# 2_MCU.net
KiCad netlist of a schematic drawn in Altium Designer
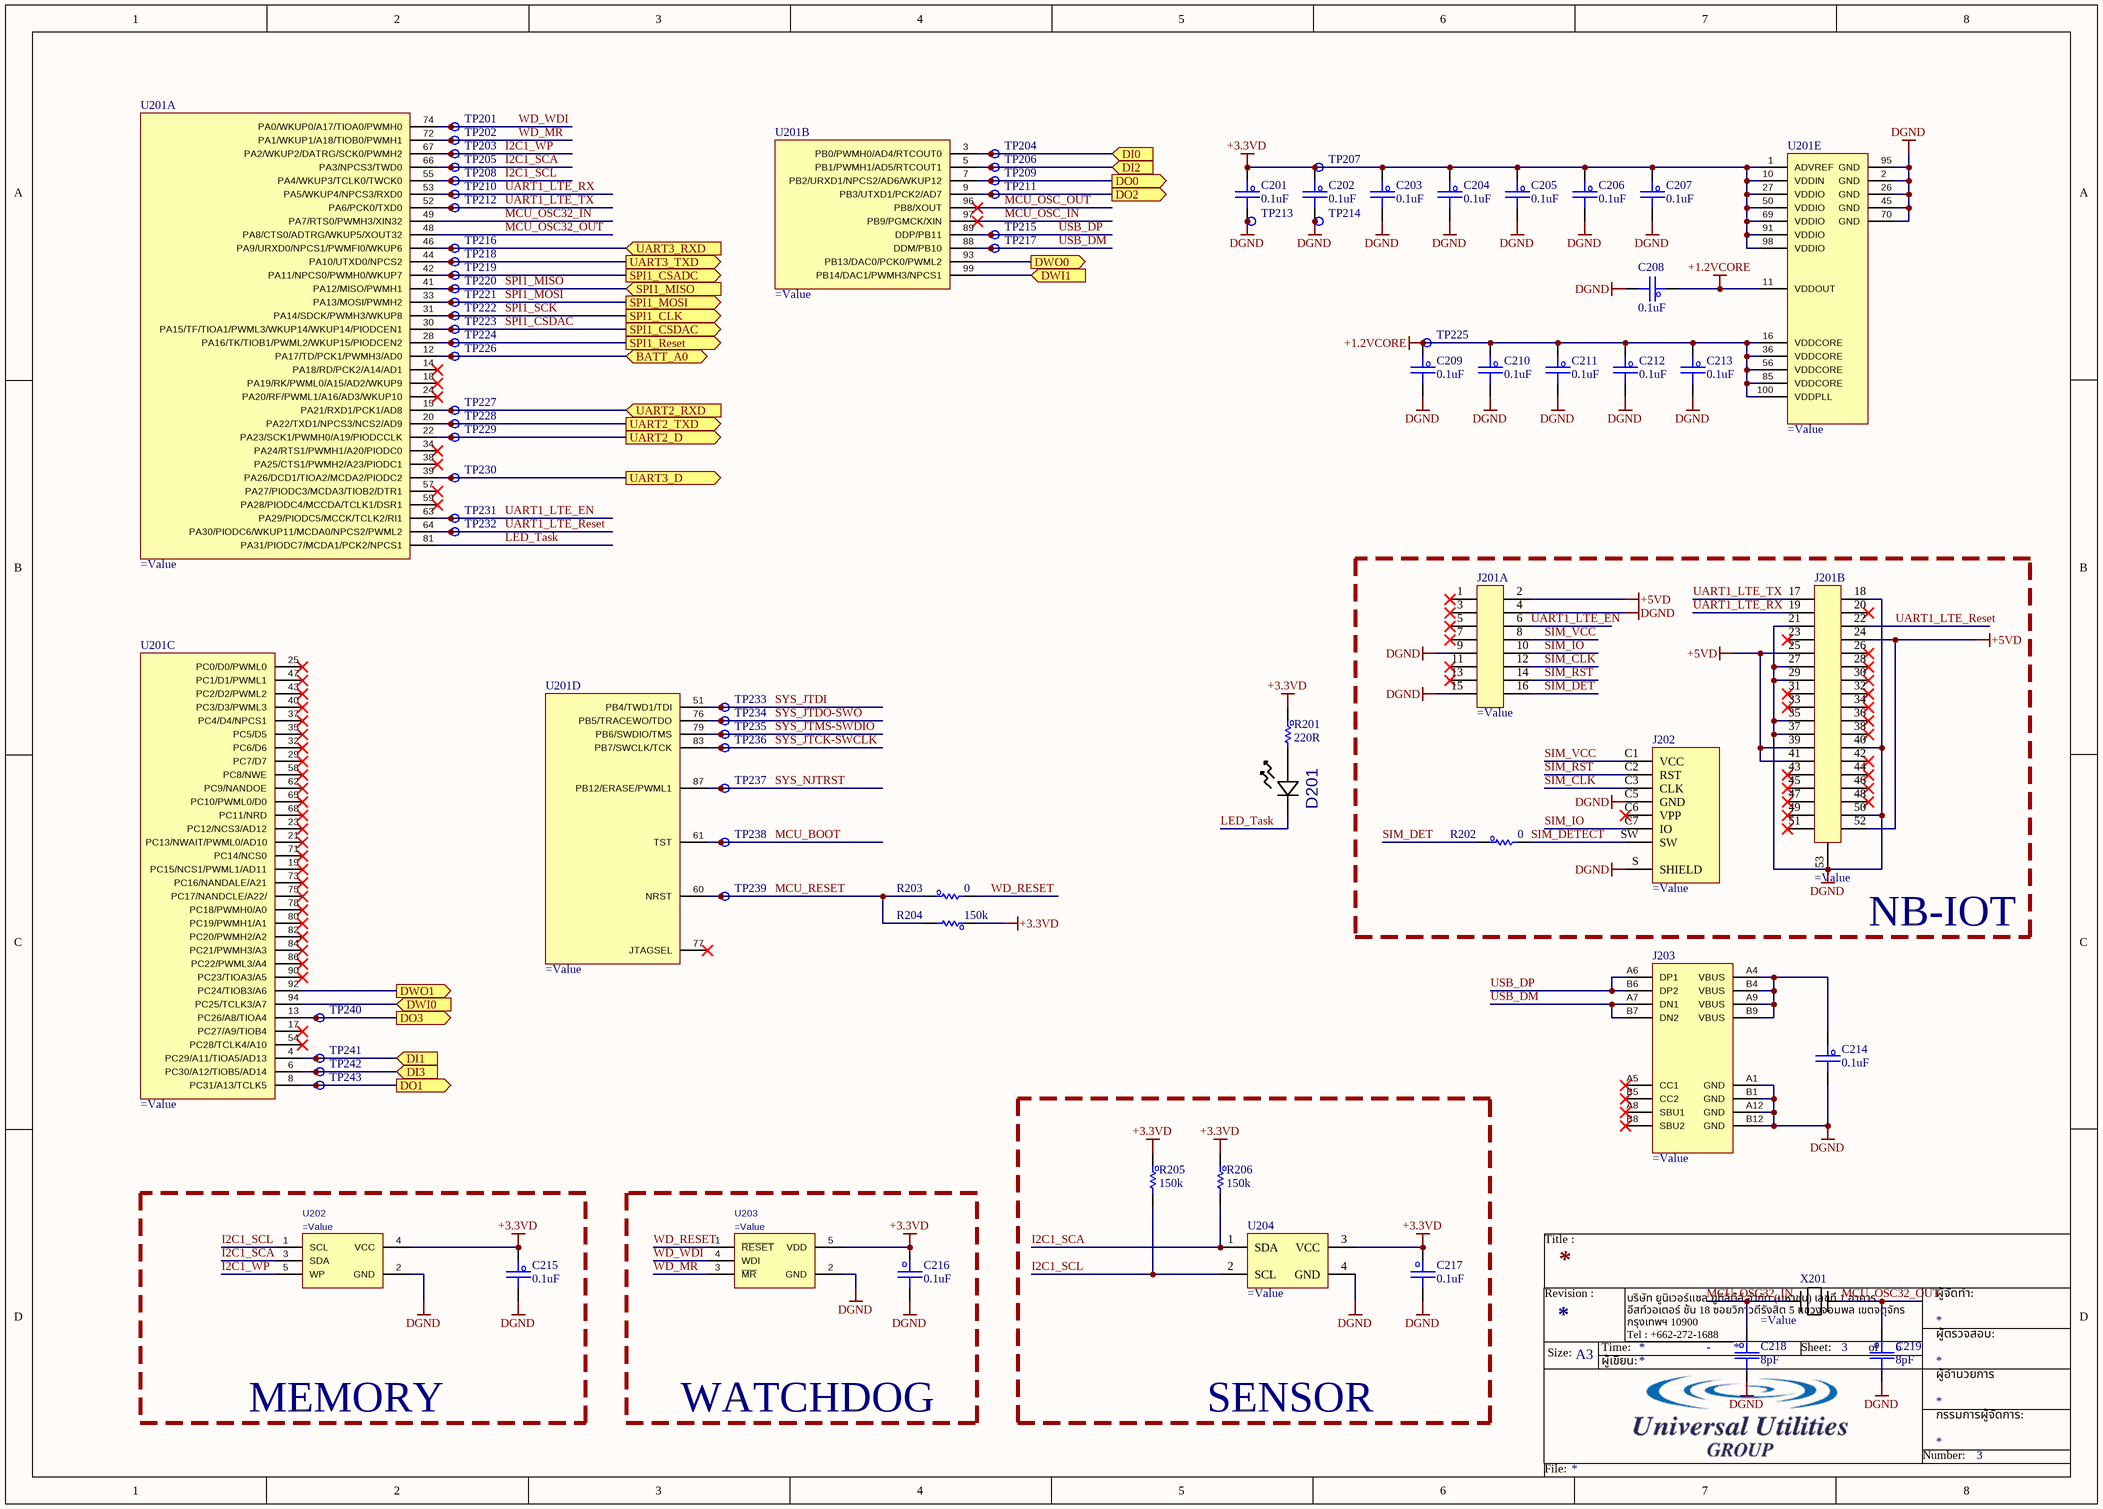
[diagram p0: 2_MCU.SchDoc]

(export (version "E")
  (design (tool "Eeschema 10.0.6"))
  (components
    (comp (ref "C201")
      (value "0.1uF")
      (footprint "C_0603")
      (description "CAP CER 0.1UF 50V X7R 0603")
      (fields (field (name "MANUFACTURER") "KEMET") (field (name "PARTNUMBER") "C0603C104K5RACTU"))
      (libsource (lib "UUSymbol") (part "C_Capacitor"))
    )
    (comp (ref "C202")
      (value "0.1uF")
      (footprint "C_0603")
      (description "CAP CER 0.1UF 50V X7R 0603")
      (fields (field (name "MANUFACTURER") "KEMET") (field (name "PARTNUMBER") "C0603C104K5RACTU"))
      (libsource (lib "UUSymbol") (part "C_Capacitor"))
    )
    (comp (ref "C203")
      (value "0.1uF")
      (footprint "C_0603")
      (description "CAP CER 0.1UF 50V X7R 0603")
      (fields (field (name "MANUFACTURER") "KEMET") (field (name "PARTNUMBER") "C0603C104K5RACTU"))
      (libsource (lib "UUSymbol") (part "C_Capacitor"))
    )
    (comp (ref "C204")
      (value "0.1uF")
      (footprint "C_0603")
      (description "CAP CER 0.1UF 50V X7R 0603")
      (fields (field (name "MANUFACTURER") "KEMET") (field (name "PARTNUMBER") "C0603C104K5RACTU"))
      (libsource (lib "UUSymbol") (part "C_Capacitor"))
    )
    (comp (ref "C205")
      (value "0.1uF")
      (footprint "C_0603")
      (description "CAP CER 0.1UF 50V X7R 0603")
      (fields (field (name "MANUFACTURER") "KEMET") (field (name "PARTNUMBER") "C0603C104K5RACTU"))
      (libsource (lib "UUSymbol") (part "C_Capacitor"))
    )
    (comp (ref "C206")
      (value "0.1uF")
      (footprint "C_0603")
      (description "CAP CER 0.1UF 50V X7R 0603")
      (fields (field (name "MANUFACTURER") "KEMET") (field (name "PARTNUMBER") "C0603C104K5RACTU"))
      (libsource (lib "UUSymbol") (part "C_Capacitor"))
    )
    (comp (ref "C207")
      (value "0.1uF")
      (footprint "C_0603")
      (description "CAP CER 0.1UF 50V X7R 0603")
      (fields (field (name "MANUFACTURER") "KEMET") (field (name "PARTNUMBER") "C0603C104K5RACTU"))
      (libsource (lib "UUSymbol") (part "C_Capacitor"))
    )
    (comp (ref "C208")
      (value "0.1uF")
      (footprint "C_0603")
      (description "CAP CER 0.1UF 50V X7R 0603")
      (fields (field (name "MANUFACTURER") "KEMET") (field (name "PARTNUMBER") "C0603C104K5RACTU"))
      (libsource (lib "UUSymbol") (part "C_Capacitor"))
    )
    (comp (ref "C209")
      (value "0.1uF")
      (footprint "C_0603")
      (description "CAP CER 0.1UF 50V X7R 0603")
      (fields (field (name "MANUFACTURER") "KEMET") (field (name "PARTNUMBER") "C0603C104K5RACTU"))
      (libsource (lib "UUSymbol") (part "C_Capacitor"))
    )
    (comp (ref "C210")
      (value "0.1uF")
      (footprint "C_0603")
      (description "CAP CER 0.1UF 50V X7R 0603")
      (fields (field (name "MANUFACTURER") "KEMET") (field (name "PARTNUMBER") "C0603C104K5RACTU"))
      (libsource (lib "UUSymbol") (part "C_Capacitor"))
    )
    (comp (ref "C211")
      (value "0.1uF")
      (footprint "C_0603")
      (description "CAP CER 0.1UF 50V X7R 0603")
      (fields (field (name "MANUFACTURER") "KEMET") (field (name "PARTNUMBER") "C0603C104K5RACTU"))
      (libsource (lib "UUSymbol") (part "C_Capacitor"))
    )
    (comp (ref "C212")
      (value "0.1uF")
      (footprint "C_0603")
      (description "CAP CER 0.1UF 50V X7R 0603")
      (fields (field (name "MANUFACTURER") "KEMET") (field (name "PARTNUMBER") "C0603C104K5RACTU"))
      (libsource (lib "UUSymbol") (part "C_Capacitor"))
    )
    (comp (ref "C213")
      (value "0.1uF")
      (footprint "C_0603")
      (description "CAP CER 0.1UF 50V X7R 0603")
      (fields (field (name "MANUFACTURER") "KEMET") (field (name "PARTNUMBER") "C0603C104K5RACTU"))
      (libsource (lib "UUSymbol") (part "C_Capacitor"))
    )
    (comp (ref "C214")
      (value "0.1uF")
      (footprint "C_0603")
      (description "CAP CER 0.1UF 50V X7R 0603")
      (fields (field (name "MANUFACTURER") "KEMET") (field (name "PARTNUMBER") "C0603C104K5RACTU"))
      (libsource (lib "UUSymbol") (part "C_Capacitor"))
    )
    (comp (ref "C215")
      (value "0.1uF")
      (footprint "C_0603")
      (description "CAP CER 0.1UF 50V X7R 0603")
      (fields (field (name "MANUFACTURER") "KEMET") (field (name "PARTNUMBER") "C0603C104K5RACTU"))
      (libsource (lib "UUSymbol") (part "C_Capacitor"))
    )
    (comp (ref "C216")
      (value "0.1uF")
      (footprint "C_0603")
      (description "CAP CER 0.1UF 50V X7R 0603")
      (fields (field (name "MANUFACTURER") "KEMET") (field (name "PARTNUMBER") "C0603C104K5RACTU"))
      (libsource (lib "UUSymbol") (part "C_Capacitor"))
    )
    (comp (ref "C217")
      (value "0.1uF")
      (footprint "C_0603")
      (description "CAP CER 0.1UF 50V X7R 0603")
      (fields (field (name "MANUFACTURER") "KEMET") (field (name "PARTNUMBER") "C0603C104K5RACTU"))
      (libsource (lib "UUSymbol") (part "C_Capacitor"))
    )
    (comp (ref "C218")
      (value "8pF")
      (footprint "C_0603")
      (description "Capacitor")
      (fields (field (name "MANUFACTURER") "KEMET") (field (name "PARTNUMBER") "CBR06C809B5GAC"))
      (libsource (lib "UUSymbol") (part "C_Capacitor"))
    )
    (comp (ref "C219")
      (value "8pF")
      (footprint "C_0603")
      (description "Capacitor")
      (fields (field (name "MANUFACTURER") "KEMET") (field (name "PARTNUMBER") "CBR06C809B5GAC"))
      (libsource (lib "UUSymbol") (part "C_Capacitor"))
    )
    (comp (ref "D201")
      (value "~")
      (footprint "LED_0VS75000_WRE")
      (description "LED BLUE CLEAR 0603 SMD")
      (fields (field (name "MANUFACTURER") "Wurth Electronics") (field (name "PARTNUMBER") "150060VS75000"))
      (libsource (lib "UUSymbol") (part "D_LED_150060BS75000"))
    )
    (comp (ref "J201")
      (value "~")
      (footprint "TE_2041119-1")
      (description "CONN PCI EXP MINI FEMALE 52POS")
      (fields
        (field (name "PARTNUMBER") "2041119-1")
        (field (name "MANUFACTURER") "TE Connectivity AMP Connectors")
      )
      (libsource (lib "UUSymbol") (part "CON_PCI-E-52P"))
    )
    (comp (ref "J202")
      (value "~")
      (footprint "SIM8060-6-1-14-00-A_REVA")
      (description "CONN SIM NANO HINGED 6P W/SWITCH")
      (fields (field (name "PARTNUMBER") "SIM8060-6-1-14-00-A") (field (name "MANUFACTURER") "GCT"))
      (libsource (lib "UUSymbol") (part "CON_SIM_Nano_Top"))
    )
    (comp (ref "J203")
      (value "~")
      (footprint "2137160001_MOL_2137160001(Primary)")
      (description "CONN RCPT USB2.0 TYPE C 24POS RA")
      (fields (field (name "PARTNUMBER") "2137160001") (field (name "MANUFACTURER") "Molex"))
      (libsource (lib "UUSymbol") (part "CON_USBC"))
    )
    (comp (ref "R201")
      (value "220R")
      (footprint "R_0603")
      (description "RES SMD 220 OHM 1% 1/10W 0603")
      (fields (field (name "MANUFACTURER") "Vishay Dale") (field (name "PARTNUMBER") "CRCW0603220RFKEAC"))
      (libsource (lib "UUSymbol") (part "R_Resister"))
    )
    (comp (ref "R202")
      (value "0")
      (footprint "R_0603")
      (description "RES SMD 0 OHM JUMP 1/10W 0603")
      (fields (field (name "MANUFACTURER") "Vishay Dale") (field (name "PARTNUMBER") "CRCW06030000Z0EBC"))
      (libsource (lib "UUSymbol") (part "R_Resister"))
    )
    (comp (ref "R203")
      (value "0")
      (footprint "R_0603")
      (description "RES SMD 0 OHM JUMP 1/10W 0603")
      (fields (field (name "MANUFACTURER") "Vishay Dale") (field (name "PARTNUMBER") "CRCW06030000Z0EBC"))
      (libsource (lib "UUSymbol") (part "R_Resister"))
    )
    (comp (ref "R204")
      (value "150k")
      (footprint "R_0603")
      (description "RES SMD 150K OHM 1% 1/10W 0603")
      (fields (field (name "MANUFACTURER") "Vishay Dale") (field (name "PARTNUMBER") "CRCW0603150KFKEAC"))
      (libsource (lib "UUSymbol") (part "R_Resister"))
    )
    (comp (ref "R205")
      (value "150k")
      (footprint "R_0603")
      (description "RES SMD 150K OHM 1% 1/10W 0603")
      (fields (field (name "MANUFACTURER") "Vishay Dale") (field (name "PARTNUMBER") "CRCW0603150KFKEAC"))
      (libsource (lib "UUSymbol") (part "R_Resister"))
    )
    (comp (ref "R206")
      (value "150k")
      (footprint "R_0603")
      (description "RES SMD 150K OHM 1% 1/10W 0603")
      (fields (field (name "MANUFACTURER") "Vishay Dale") (field (name "PARTNUMBER") "CRCW0603150KFKEAC"))
      (libsource (lib "UUSymbol") (part "R_Resister"))
    )
    (comp (ref "TP201")
      (value "~")
      (footprint "TP_Testpoint")
      (description "TestPoint")
      (libsource (lib "UUSymbol") (part "TP_TestPoint"))
    )
    (comp (ref "TP202")
      (value "~")
      (footprint "TP_Testpoint")
      (description "TestPoint")
      (libsource (lib "UUSymbol") (part "TP_TestPoint"))
    )
    (comp (ref "TP203")
      (value "~")
      (footprint "TP_Testpoint")
      (description "TestPoint")
      (libsource (lib "UUSymbol") (part "TP_TestPoint"))
    )
    (comp (ref "TP204")
      (value "~")
      (footprint "TP_Testpoint")
      (description "TestPoint")
      (libsource (lib "UUSymbol") (part "TP_TestPoint"))
    )
    (comp (ref "TP205")
      (value "~")
      (footprint "TP_Testpoint")
      (description "TestPoint")
      (libsource (lib "UUSymbol") (part "TP_TestPoint"))
    )
    (comp (ref "TP206")
      (value "~")
      (footprint "TP_Testpoint")
      (description "TestPoint")
      (libsource (lib "UUSymbol") (part "TP_TestPoint"))
    )
    (comp (ref "TP207")
      (value "~")
      (footprint "TP_Testpoint")
      (description "TestPoint")
      (libsource (lib "UUSymbol") (part "TP_TestPoint"))
    )
    (comp (ref "TP208")
      (value "~")
      (footprint "TP_Testpoint")
      (description "TestPoint")
      (libsource (lib "UUSymbol") (part "TP_TestPoint"))
    )
    (comp (ref "TP209")
      (value "~")
      (footprint "TP_Testpoint")
      (description "TestPoint")
      (libsource (lib "UUSymbol") (part "TP_TestPoint"))
    )
    (comp (ref "TP210")
      (value "~")
      (footprint "TP_Testpoint")
      (description "TestPoint")
      (libsource (lib "UUSymbol") (part "TP_TestPoint"))
    )
    (comp (ref "TP211")
      (value "~")
      (footprint "TP_Testpoint")
      (description "TestPoint")
      (libsource (lib "UUSymbol") (part "TP_TestPoint"))
    )
    (comp (ref "TP212")
      (value "~")
      (footprint "TP_Testpoint")
      (description "TestPoint")
      (libsource (lib "UUSymbol") (part "TP_TestPoint"))
    )
    (comp (ref "TP213")
      (value "~")
      (footprint "TP_Testpoint")
      (description "TestPoint")
      (libsource (lib "UUSymbol") (part "TP_TestPoint"))
    )
    (comp (ref "TP214")
      (value "~")
      (footprint "TP_Testpoint")
      (description "TestPoint")
      (libsource (lib "UUSymbol") (part "TP_TestPoint"))
    )
    (comp (ref "TP215")
      (value "~")
      (footprint "TP_Testpoint")
      (description "TestPoint")
      (libsource (lib "UUSymbol") (part "TP_TestPoint"))
    )
    (comp (ref "TP216")
      (value "~")
      (footprint "TP_Testpoint")
      (description "TestPoint")
      (libsource (lib "UUSymbol") (part "TP_TestPoint"))
    )
    (comp (ref "TP217")
      (value "~")
      (footprint "TP_Testpoint")
      (description "TestPoint")
      (libsource (lib "UUSymbol") (part "TP_TestPoint"))
    )
    (comp (ref "TP218")
      (value "~")
      (footprint "TP_Testpoint")
      (description "TestPoint")
      (libsource (lib "UUSymbol") (part "TP_TestPoint"))
    )
    (comp (ref "TP219")
      (value "~")
      (footprint "TP_Testpoint")
      (description "TestPoint")
      (libsource (lib "UUSymbol") (part "TP_TestPoint"))
    )
    (comp (ref "TP220")
      (value "~")
      (footprint "TP_Testpoint")
      (description "TestPoint")
      (libsource (lib "UUSymbol") (part "TP_TestPoint"))
    )
    (comp (ref "TP221")
      (value "~")
      (footprint "TP_Testpoint")
      (description "TestPoint")
      (libsource (lib "UUSymbol") (part "TP_TestPoint"))
    )
    (comp (ref "TP222")
      (value "~")
      (footprint "TP_Testpoint")
      (description "TestPoint")
      (libsource (lib "UUSymbol") (part "TP_TestPoint"))
    )
    (comp (ref "TP223")
      (value "~")
      (footprint "TP_Testpoint")
      (description "TestPoint")
      (libsource (lib "UUSymbol") (part "TP_TestPoint"))
    )
    (comp (ref "TP224")
      (value "~")
      (footprint "TP_Testpoint")
      (description "TestPoint")
      (libsource (lib "UUSymbol") (part "TP_TestPoint"))
    )
    (comp (ref "TP225")
      (value "~")
      (footprint "TP_Testpoint")
      (description "TestPoint")
      (libsource (lib "UUSymbol") (part "TP_TestPoint"))
    )
    (comp (ref "TP226")
      (value "~")
      (footprint "TP_Testpoint")
      (description "TestPoint")
      (libsource (lib "UUSymbol") (part "TP_TestPoint"))
    )
    (comp (ref "TP227")
      (value "~")
      (footprint "TP_Testpoint")
      (description "TestPoint")
      (libsource (lib "UUSymbol") (part "TP_TestPoint"))
    )
    (comp (ref "TP228")
      (value "~")
      (footprint "TP_Testpoint")
      (description "TestPoint")
      (libsource (lib "UUSymbol") (part "TP_TestPoint"))
    )
    (comp (ref "TP229")
      (value "~")
      (footprint "TP_Testpoint")
      (description "TestPoint")
      (libsource (lib "UUSymbol") (part "TP_TestPoint"))
    )
    (comp (ref "TP230")
      (value "~")
      (footprint "TP_Testpoint")
      (description "TestPoint")
      (libsource (lib "UUSymbol") (part "TP_TestPoint"))
    )
    (comp (ref "TP231")
      (value "~")
      (footprint "TP_Testpoint")
      (description "TestPoint")
      (libsource (lib "UUSymbol") (part "TP_TestPoint"))
    )
    (comp (ref "TP232")
      (value "~")
      (footprint "TP_Testpoint")
      (description "TestPoint")
      (libsource (lib "UUSymbol") (part "TP_TestPoint"))
    )
    (comp (ref "TP233")
      (value "~")
      (footprint "TP_Testpoint")
      (description "TestPoint")
      (libsource (lib "UUSymbol") (part "TP_TestPoint"))
    )
    (comp (ref "TP234")
      (value "~")
      (footprint "TP_Testpoint")
      (description "TestPoint")
      (libsource (lib "UUSymbol") (part "TP_TestPoint"))
    )
    (comp (ref "TP235")
      (value "~")
      (footprint "TP_Testpoint")
      (description "TestPoint")
      (libsource (lib "UUSymbol") (part "TP_TestPoint"))
    )
    (comp (ref "TP236")
      (value "~")
      (footprint "TP_Testpoint")
      (description "TestPoint")
      (libsource (lib "UUSymbol") (part "TP_TestPoint"))
    )
    (comp (ref "TP237")
      (value "~")
      (footprint "TP_Testpoint")
      (description "TestPoint")
      (libsource (lib "UUSymbol") (part "TP_TestPoint"))
    )
    (comp (ref "TP238")
      (value "~")
      (footprint "TP_Testpoint")
      (description "TestPoint")
      (libsource (lib "UUSymbol") (part "TP_TestPoint"))
    )
    (comp (ref "TP239")
      (value "~")
      (footprint "TP_Testpoint")
      (description "TestPoint")
      (libsource (lib "UUSymbol") (part "TP_TestPoint"))
    )
    (comp (ref "TP240")
      (value "~")
      (footprint "TP_Testpoint")
      (description "TestPoint")
      (libsource (lib "UUSymbol") (part "TP_TestPoint"))
    )
    (comp (ref "TP241")
      (value "~")
      (footprint "TP_Testpoint")
      (description "TestPoint")
      (libsource (lib "UUSymbol") (part "TP_TestPoint"))
    )
    (comp (ref "TP242")
      (value "~")
      (footprint "TP_Testpoint")
      (description "TestPoint")
      (libsource (lib "UUSymbol") (part "TP_TestPoint"))
    )
    (comp (ref "TP243")
      (value "~")
      (footprint "TP_Testpoint")
      (description "TestPoint")
      (libsource (lib "UUSymbol") (part "TP_TestPoint"))
    )
    (comp (ref "U201")
      (value "~")
      (footprint "TQFP100_14X14M00")
      (description "IC MCU 32BIT 1MB FLASH 100LQFP")
      (fields
        (field (name "MANUFACTURER") "Microchip Technology")
        (field (name "PARTNUMBER") "ATSAM4SA16CA-AUR")
      )
      (libsource (lib "UUSymbol") (part "IC_MCU_ATSAM4SA16CA"))
    )
    (comp (ref "U202")
      (value "~")
      (footprint "SOT65P210X110-5N")
      (description "IC EEPROM 2KBIT I2C SC70-5")
      (fields
        (field (name "MANUFACTURER") "Microchip Technology")
        (field (name "PARTNUMBER") "24AA02HT-I/LT")
      )
      (libsource (lib "UUSymbol") (part "IC_MEM_24AA02HT"))
    )
    (comp (ref "U203")
      (value "~")
      (footprint "DBV5")
      (description "Processor Supervisory Circuits")
      (fields
        (field (name "MANUFACTURER") "Texas Instruments")
        (field (name "PARTNUMBER") "TPS3828-33DBVTG4")
      )
      (libsource (lib "UUSymbol") (part "IC_WDT_TPS3828-33DBVTG4"))
    )
    (comp (ref "U204")
      (value "~")
      (footprint "XDCR_SHT40-AD1B-R2")
      (description "SENSOR HUMIDITY 100 RH SMD")
      (fields (field (name "PARTNUMBER") "SHT40-AD1B-R3") (field (name "MANUFACTURER") "Sensirion AG"))
      (libsource (lib "UUSymbol") (part "IC_SEN_SHT40-AD1B-R3"))
    )
    (comp (ref "X201")
      (value "~")
      (footprint "XTAL_CM315D_CF00")
      (description "CRYSTAL 32.7680KHZ 7PF SMD")
      (fields
        (field (name "PARTNUMBER") "CM315D32768DZYT")
        (field (name "MANUFACTURER") "Citizen Finedevice Co Ltd")
      )
      (libsource (lib "UUSymbol") (part "X_32_768MHz"))
    )
  )
  (nets
    (net (code "1") (name "+1.2VCORE") (class "Default")
      (node (ref "C208") (pin "1") (pinfunction "1_1") (pintype "passive"))
      (node (ref "C209") (pin "1") (pinfunction "1_1") (pintype "passive"))
      (node (ref "C210") (pin "1") (pinfunction "1_1") (pintype "passive"))
      (node (ref "C211") (pin "1") (pinfunction "1_1") (pintype "passive"))
      (node (ref "C212") (pin "1") (pinfunction "1_1") (pintype "passive"))
      (node (ref "C213") (pin "1") (pinfunction "1_1") (pintype "passive"))
      (node (ref "TP225") (pin "1") (pinfunction "1_1") (pintype "passive"))
      (node (ref "U201") (pin "100") (pinfunction "VDDPLL_100") (pintype "passive"))
      (node (ref "U201") (pin "11") (pinfunction "VDDOUT_11") (pintype "passive"))
      (node (ref "U201") (pin "16") (pinfunction "VDDCORE_16") (pintype "passive"))
      (node (ref "U201") (pin "36") (pinfunction "VDDCORE_36") (pintype "passive"))
      (node (ref "U201") (pin "56") (pinfunction "VDDCORE_56") (pintype "passive"))
      (node (ref "U201") (pin "85") (pinfunction "VDDCORE_85") (pintype "passive"))
    )
    (net (code "2") (name "+3.3VD") (class "Default")
      (node (ref "C201") (pin "1") (pinfunction "1_1") (pintype "passive"))
      (node (ref "C202") (pin "1") (pinfunction "1_1") (pintype "passive"))
      (node (ref "C203") (pin "1") (pinfunction "1_1") (pintype "passive"))
      (node (ref "C204") (pin "1") (pinfunction "1_1") (pintype "passive"))
      (node (ref "C205") (pin "1") (pinfunction "1_1") (pintype "passive"))
      (node (ref "C206") (pin "1") (pinfunction "1_1") (pintype "passive"))
      (node (ref "C207") (pin "1") (pinfunction "1_1") (pintype "passive"))
      (node (ref "C215") (pin "1") (pinfunction "1_1") (pintype "passive"))
      (node (ref "C216") (pin "1") (pinfunction "1_1") (pintype "passive"))
      (node (ref "C217") (pin "1") (pinfunction "1_1") (pintype "passive"))
      (node (ref "R201") (pin "1") (pinfunction "1_1") (pintype "passive"))
      (node (ref "R204") (pin "1") (pinfunction "1_1") (pintype "passive"))
      (node (ref "R205") (pin "1") (pinfunction "1_1") (pintype "passive"))
      (node (ref "R206") (pin "1") (pinfunction "1_1") (pintype "passive"))
      (node (ref "TP207") (pin "1") (pinfunction "1_1") (pintype "passive"))
      (node (ref "U201") (pin "1") (pinfunction "ADVREF_1") (pintype "passive"))
      (node (ref "U201") (pin "10") (pinfunction "VDDIN_10") (pintype "passive"))
      (node (ref "U201") (pin "27") (pinfunction "VDDIO_27") (pintype "passive"))
      (node (ref "U201") (pin "50") (pinfunction "VDDIO_50") (pintype "passive"))
      (node (ref "U201") (pin "69") (pinfunction "VDDIO_69") (pintype "passive"))
      (node (ref "U201") (pin "91") (pinfunction "VDDIO_91") (pintype "passive"))
      (node (ref "U201") (pin "98") (pinfunction "VDDIO_98") (pintype "passive"))
      (node (ref "U202") (pin "4") (pinfunction "VCC_4") (pintype "passive"))
      (node (ref "U203") (pin "5") (pinfunction "VDD_5") (pintype "power_in"))
      (node (ref "U204") (pin "3") (pinfunction "VCC_3") (pintype "passive"))
    )
    (net (code "3") (name "+5VD") (class "Default")
      (node (ref "J201") (pin "2") (pinfunction "2_2") (pintype "passive"))
      (node (ref "J201") (pin "24") (pinfunction "24_24") (pintype "passive"))
      (node (ref "J201") (pin "25") (pinfunction "25_25") (pintype "passive"))
      (node (ref "J201") (pin "39") (pinfunction "39_39") (pintype "passive"))
      (node (ref "J201") (pin "41") (pinfunction "41_41") (pintype "passive"))
      (node (ref "J201") (pin "52") (pinfunction "52_52") (pintype "passive"))
    )
    (net (code "4") (name "/BATT_A0") (class "Default")
      (node (ref "TP226") (pin "1") (pinfunction "1_1") (pintype "passive"))
      (node (ref "U201") (pin "12") (pinfunction "PA17/TD/PCK1/PWMH3/AD0_12") (pintype "passive"))
    )
    (net (code "5") (name "/DI0") (class "Default")
      (node (ref "TP204") (pin "1") (pinfunction "1_1") (pintype "passive"))
      (node (ref "U201") (pin "3") (pinfunction "PB0/PWMH0/AD4/RTCOUT0_3") (pintype "passive"))
    )
    (net (code "6") (name "/DI1") (class "Default")
      (node (ref "TP241") (pin "1") (pinfunction "1_1") (pintype "passive"))
      (node (ref "U201") (pin "4") (pinfunction "PC29/A11/TIOA5/AD13_4") (pintype "passive"))
    )
    (net (code "7") (name "/DI2") (class "Default")
      (node (ref "TP206") (pin "1") (pinfunction "1_1") (pintype "passive"))
      (node (ref "U201") (pin "5") (pinfunction "PB1/PWMH1/AD5/RTCOUT1_5") (pintype "passive"))
    )
    (net (code "8") (name "/DI3") (class "Default")
      (node (ref "TP242") (pin "1") (pinfunction "1_1") (pintype "passive"))
      (node (ref "U201") (pin "6") (pinfunction "PC30/A12/TIOB5/AD14_6") (pintype "passive"))
    )
    (net (code "9") (name "/DO0") (class "Default")
      (node (ref "TP209") (pin "1") (pinfunction "1_1") (pintype "passive"))
      (node (ref "U201") (pin "7") (pinfunction "PB2/URXD1/NPCS2/AD6/WKUP12_7") (pintype "passive"))
    )
    (net (code "10") (name "/DO1") (class "Default")
      (node (ref "TP243") (pin "1") (pinfunction "1_1") (pintype "passive"))
      (node (ref "U201") (pin "8") (pinfunction "PC31/A13/TCLK5_8") (pintype "passive"))
    )
    (net (code "11") (name "/DO2") (class "Default")
      (node (ref "TP211") (pin "1") (pinfunction "1_1") (pintype "passive"))
      (node (ref "U201") (pin "9") (pinfunction "PB3/UTXD1/PCK2/AD7_9") (pintype "passive"))
    )
    (net (code "12") (name "/DO3") (class "Default")
      (node (ref "TP240") (pin "1") (pinfunction "1_1") (pintype "passive"))
      (node (ref "U201") (pin "13") (pinfunction "PC26/A8/TIOA4_13") (pintype "passive"))
    )
    (net (code "13") (name "/DWI0") (class "Default")
      (node (ref "U201") (pin "94") (pinfunction "PC25/TCLK3/A7_94") (pintype "passive"))
    )
    (net (code "14") (name "/DWI1") (class "Default")
      (node (ref "U201") (pin "99") (pinfunction "PB14/DAC1/PWMH3/NPCS1_99") (pintype "passive"))
    )
    (net (code "15") (name "/DWO0") (class "Default")
      (node (ref "U201") (pin "93") (pinfunction "PB13/DAC0/PCK0/PWML2_93") (pintype "passive"))
    )
    (net (code "16") (name "/DWO1") (class "Default")
      (node (ref "U201") (pin "92") (pinfunction "PC24/TIOB3/A6_92") (pintype "passive"))
    )
    (net (code "17") (name "/I2C1_SCA") (class "Default")
      (node (ref "R206") (pin "2") (pinfunction "2_2") (pintype "passive"))
      (node (ref "TP205") (pin "1") (pinfunction "1_1") (pintype "passive"))
      (node (ref "U201") (pin "66") (pinfunction "PA3/NPCS3/TWD0_66") (pintype "passive"))
      (node (ref "U202") (pin "3") (pinfunction "SDA_3") (pintype "passive"))
      (node (ref "U204") (pin "1") (pinfunction "SDA_1") (pintype "passive"))
    )
    (net (code "18") (name "/I2C1_SCL") (class "Default")
      (node (ref "R205") (pin "2") (pinfunction "2_2") (pintype "passive"))
      (node (ref "TP208") (pin "1") (pinfunction "1_1") (pintype "passive"))
      (node (ref "U201") (pin "55") (pinfunction "PA4/WKUP3/TCLK0/TWCK0_55") (pintype "passive"))
      (node (ref "U202") (pin "1") (pinfunction "SCL_1") (pintype "passive"))
      (node (ref "U204") (pin "2") (pinfunction "SCL_2") (pintype "passive"))
    )
    (net (code "19") (name "/I2C1_WP") (class "Default")
      (node (ref "TP203") (pin "1") (pinfunction "1_1") (pintype "passive"))
      (node (ref "U201") (pin "67") (pinfunction "PA2/WKUP2/DATRG/SCK0/PWMH2_67") (pintype "passive"))
      (node (ref "U202") (pin "5") (pinfunction "WP_5") (pintype "passive"))
    )
    (net (code "20") (name "/LED_Task") (class "Default")
      (node (ref "D201") (pin "1") (pinfunction "1_1") (pintype "passive"))
      (node (ref "U201") (pin "81") (pinfunction "PA31/PIODC7/MCDA1/PCK2/NPCS1_81") (pintype "passive"))
    )
    (net (code "21") (name "/MCU_BOOT") (class "Default")
      (node (ref "TP238") (pin "1") (pinfunction "1_1") (pintype "passive"))
      (node (ref "U201") (pin "61") (pinfunction "TST_61") (pintype "passive"))
    )
    (net (code "22") (name "/MCU_OSC32_IN") (class "Default")
      (node (ref "C218") (pin "1") (pinfunction "1_1") (pintype "passive"))
      (node (ref "U201") (pin "49") (pinfunction "PA7/RTS0/PWMH3/XIN32_49") (pintype "passive"))
      (node (ref "X201") (pin "1") (pinfunction "1_1") (pintype "passive"))
    )
    (net (code "23") (name "/MCU_OSC32_OUT") (class "Default")
      (node (ref "C219") (pin "1") (pinfunction "1_1") (pintype "passive"))
      (node (ref "U201") (pin "48") (pinfunction "PA8/CTS0/ADTRG/WKUP5/XOUT32_48") (pintype "passive"))
      (node (ref "X201") (pin "2") (pinfunction "2_2") (pintype "passive"))
    )
    (net (code "24") (name "/MCU_OSC_IN") (class "Default")
      (node (ref "U201") (pin "97") (pinfunction "PB9/PGMCK/XIN_97") (pintype "passive+no_connect"))
    )
    (net (code "25") (name "/MCU_OSC_OUT") (class "Default")
      (node (ref "U201") (pin "96") (pinfunction "PB8/XOUT_96") (pintype "passive+no_connect"))
    )
    (net (code "26") (name "/MCU_RESET") (class "Default")
      (node (ref "R203") (pin "1") (pinfunction "1_1") (pintype "passive"))
      (node (ref "R204") (pin "2") (pinfunction "2_2") (pintype "passive"))
      (node (ref "TP239") (pin "1") (pinfunction "1_1") (pintype "passive"))
      (node (ref "U201") (pin "60") (pinfunction "NRST_60") (pintype "passive"))
    )
    (net (code "27") (name "/SIM_CLK") (class "Default")
      (node (ref "J201") (pin "12") (pinfunction "12_12") (pintype "passive"))
      (node (ref "J202") (pin "C3") (pinfunction "CLK_C3") (pintype "passive"))
    )
    (net (code "28") (name "/SIM_DET") (class "Default")
      (node (ref "J201") (pin "16") (pinfunction "16_16") (pintype "passive"))
      (node (ref "R202") (pin "1") (pinfunction "1_1") (pintype "passive"))
    )
    (net (code "29") (name "/SIM_DETECT") (class "Default")
      (node (ref "J202") (pin "SW") (pinfunction "SW_SW") (pintype "passive"))
      (node (ref "R202") (pin "2") (pinfunction "2_2") (pintype "passive"))
    )
    (net (code "30") (name "/SIM_IO") (class "Default")
      (node (ref "J201") (pin "10") (pinfunction "10_10") (pintype "passive"))
      (node (ref "J202") (pin "C7") (pinfunction "IO_C7") (pintype "passive"))
    )
    (net (code "31") (name "/SIM_RST") (class "Default")
      (node (ref "J201") (pin "14") (pinfunction "14_14") (pintype "passive"))
      (node (ref "J202") (pin "C2") (pinfunction "RST_C2") (pintype "passive"))
    )
    (net (code "32") (name "/SIM_VCC") (class "Default")
      (node (ref "J201") (pin "8") (pinfunction "8_8") (pintype "passive"))
      (node (ref "J202") (pin "C1") (pinfunction "VCC_C1") (pintype "passive"))
    )
    (net (code "33") (name "/SPI1_CSADC") (class "Default")
      (node (ref "TP219") (pin "1") (pinfunction "1_1") (pintype "passive"))
      (node (ref "U201") (pin "42") (pinfunction "PA11/NPCS0/PWMH0/WKUP7_42") (pintype "passive"))
    )
    (net (code "34") (name "/SPI1_CSDAC") (class "Default")
      (node (ref "TP223") (pin "1") (pinfunction "1_1") (pintype "passive"))
      (node (ref "U201") (pin "30") (pinfunction "PA15/TF/TIOA1/PWML3/WKUP14/WKUP14/PIODCEN1_30") (pintype "passive"))
    )
    (net (code "35") (name "/SPI1_MISO") (class "Default")
      (node (ref "TP220") (pin "1") (pinfunction "1_1") (pintype "passive"))
      (node (ref "U201") (pin "41") (pinfunction "PA12/MISO/PWMH1_41") (pintype "passive"))
    )
    (net (code "36") (name "/SPI1_MOSI") (class "Default")
      (node (ref "TP221") (pin "1") (pinfunction "1_1") (pintype "passive"))
      (node (ref "U201") (pin "33") (pinfunction "PA13/MOSI/PWMH2_33") (pintype "passive"))
    )
    (net (code "37") (name "/SPI1_Reset") (class "Default")
      (node (ref "TP224") (pin "1") (pinfunction "1_1") (pintype "passive"))
      (node (ref "U201") (pin "28") (pinfunction "PA16/TK/TIOB1/PWML2/WKUP15/PIODCEN2_28") (pintype "passive"))
    )
    (net (code "38") (name "/SPI1_SCK") (class "Default")
      (node (ref "TP222") (pin "1") (pinfunction "1_1") (pintype "passive"))
      (node (ref "U201") (pin "31") (pinfunction "PA14/SDCK/PWMH3/WKUP8_31") (pintype "passive"))
    )
    (net (code "39") (name "/SYS_JTCK-SWCLK") (class "Default")
      (node (ref "TP236") (pin "1") (pinfunction "1_1") (pintype "passive"))
      (node (ref "U201") (pin "83") (pinfunction "PB7/SWCLK/TCK_83") (pintype "passive"))
    )
    (net (code "40") (name "/SYS_JTDI") (class "Default")
      (node (ref "TP233") (pin "1") (pinfunction "1_1") (pintype "passive"))
      (node (ref "U201") (pin "51") (pinfunction "PB4/TWD1/TDI_51") (pintype "passive"))
    )
    (net (code "41") (name "/SYS_JTDO-SWO") (class "Default")
      (node (ref "TP234") (pin "1") (pinfunction "1_1") (pintype "passive"))
      (node (ref "U201") (pin "76") (pinfunction "PB5/TRACEWO/TDO_76") (pintype "passive"))
    )
    (net (code "42") (name "/SYS_JTMS-SWDIO") (class "Default")
      (node (ref "TP235") (pin "1") (pinfunction "1_1") (pintype "passive"))
      (node (ref "U201") (pin "79") (pinfunction "PB6/SWDIO/TMS_79") (pintype "passive"))
    )
    (net (code "43") (name "/SYS_NJTRST") (class "Default")
      (node (ref "TP237") (pin "1") (pinfunction "1_1") (pintype "passive"))
      (node (ref "U201") (pin "87") (pinfunction "PB12/ERASE/PWML1_87") (pintype "passive"))
    )
    (net (code "44") (name "/UART1_LTE_EN") (class "Default")
      (node (ref "J201") (pin "6") (pinfunction "6_6") (pintype "passive"))
      (node (ref "TP231") (pin "1") (pinfunction "1_1") (pintype "passive"))
      (node (ref "U201") (pin "63") (pinfunction "PA29/PIODC5/MCCK/TCLK2/RI1_63") (pintype "passive"))
    )
    (net (code "45") (name "/UART1_LTE_RX") (class "Default")
      (node (ref "J201") (pin "19") (pinfunction "19_19") (pintype "passive"))
      (node (ref "TP210") (pin "1") (pinfunction "1_1") (pintype "passive"))
      (node (ref "U201") (pin "53") (pinfunction "PA5/WKUP4/NPCS3/RXD0_53") (pintype "passive"))
    )
    (net (code "46") (name "/UART1_LTE_Reset") (class "Default")
      (node (ref "J201") (pin "22") (pinfunction "22_22") (pintype "passive"))
      (node (ref "TP232") (pin "1") (pinfunction "1_1") (pintype "passive"))
      (node (ref "U201") (pin "64") (pinfunction "PA30/PIODC6/WKUP11/MCDA0/NPCS2/PWML2_64") (pintype "passive"))
    )
    (net (code "47") (name "/UART1_LTE_TX") (class "Default")
      (node (ref "J201") (pin "17") (pinfunction "17_17") (pintype "passive"))
      (node (ref "TP212") (pin "1") (pinfunction "1_1") (pintype "passive"))
      (node (ref "U201") (pin "52") (pinfunction "PA6/PCK0/TXD0_52") (pintype "passive"))
    )
    (net (code "48") (name "/UART2_D") (class "Default")
      (node (ref "TP229") (pin "1") (pinfunction "1_1") (pintype "passive"))
      (node (ref "U201") (pin "22") (pinfunction "PA23/SCK1/PWMH0/A19/PIODCCLK_22") (pintype "passive"))
    )
    (net (code "49") (name "/UART2_RXD") (class "Default")
      (node (ref "TP227") (pin "1") (pinfunction "1_1") (pintype "passive"))
      (node (ref "U201") (pin "15") (pinfunction "PA21/RXD1/PCK1/AD8_15") (pintype "passive"))
    )
    (net (code "50") (name "/UART2_TXD") (class "Default")
      (node (ref "TP228") (pin "1") (pinfunction "1_1") (pintype "passive"))
      (node (ref "U201") (pin "20") (pinfunction "PA22/TXD1/NPCS3/NCS2/AD9_20") (pintype "passive"))
    )
    (net (code "51") (name "/UART3_D") (class "Default")
      (node (ref "TP230") (pin "1") (pinfunction "1_1") (pintype "passive"))
      (node (ref "U201") (pin "39") (pinfunction "PA26/DCD1/TIOA2/MCDA2/PIODC2_39") (pintype "passive"))
    )
    (net (code "52") (name "/UART3_RXD") (class "Default")
      (node (ref "TP216") (pin "1") (pinfunction "1_1") (pintype "passive"))
      (node (ref "U201") (pin "46") (pinfunction "PA9/URXD0/NPCS1/PWMFI0/WKUP6_46") (pintype "passive"))
    )
    (net (code "53") (name "/UART3_TXD") (class "Default")
      (node (ref "TP218") (pin "1") (pinfunction "1_1") (pintype "passive"))
      (node (ref "U201") (pin "44") (pinfunction "PA10/UTXD0/NPCS2_44") (pintype "passive"))
    )
    (net (code "54") (name "/USB_DM") (class "Default")
      (node (ref "J203") (pin "A7") (pinfunction "DN1_A7") (pintype "passive"))
      (node (ref "J203") (pin "B7") (pinfunction "DN2_B7") (pintype "passive"))
      (node (ref "TP217") (pin "1") (pinfunction "1_1") (pintype "passive"))
      (node (ref "U201") (pin "88") (pinfunction "DDM/PB10_88") (pintype "passive"))
    )
    (net (code "55") (name "/USB_DP") (class "Default")
      (node (ref "J203") (pin "A6") (pinfunction "DP1_A6") (pintype "passive"))
      (node (ref "J203") (pin "B6") (pinfunction "DP2_B6") (pintype "passive"))
      (node (ref "TP215") (pin "1") (pinfunction "1_1") (pintype "passive"))
      (node (ref "U201") (pin "89") (pinfunction "DDP/PB11_89") (pintype "passive"))
    )
    (net (code "56") (name "/WD_MR") (class "Default")
      (node (ref "TP202") (pin "1") (pinfunction "1_1") (pintype "passive"))
      (node (ref "U201") (pin "72") (pinfunction "PA1/WKUP1/A18/TIOB0/PWMH1_72") (pintype "passive"))
      (node (ref "U203") (pin "3") (pinfunction "~{MR}_3") (pintype "passive"))
    )
    (net (code "57") (name "/WD_RESET") (class "Default")
      (node (ref "R203") (pin "2") (pinfunction "2_2") (pintype "passive"))
      (node (ref "U203") (pin "1") (pinfunction "~{RESET}_1") (pintype "passive"))
    )
    (net (code "58") (name "/WD_WDI") (class "Default")
      (node (ref "TP201") (pin "1") (pinfunction "1_1") (pintype "passive"))
      (node (ref "U201") (pin "74") (pinfunction "PA0/WKUP0/A17/TIOA0/PWMH0_74") (pintype "passive"))
      (node (ref "U203") (pin "4") (pinfunction "WDI_4") (pintype "passive"))
    )
    (net (code "59") (name "DGND") (class "Default")
      (node (ref "C201") (pin "2") (pinfunction "2_2") (pintype "passive"))
      (node (ref "C202") (pin "2") (pinfunction "2_2") (pintype "passive"))
      (node (ref "C203") (pin "2") (pinfunction "2_2") (pintype "passive"))
      (node (ref "C204") (pin "2") (pinfunction "2_2") (pintype "passive"))
      (node (ref "C205") (pin "2") (pinfunction "2_2") (pintype "passive"))
      (node (ref "C206") (pin "2") (pinfunction "2_2") (pintype "passive"))
      (node (ref "C207") (pin "2") (pinfunction "2_2") (pintype "passive"))
      (node (ref "C208") (pin "2") (pinfunction "2_2") (pintype "passive"))
      (node (ref "C209") (pin "2") (pinfunction "2_2") (pintype "passive"))
      (node (ref "C210") (pin "2") (pinfunction "2_2") (pintype "passive"))
      (node (ref "C211") (pin "2") (pinfunction "2_2") (pintype "passive"))
      (node (ref "C212") (pin "2") (pinfunction "2_2") (pintype "passive"))
      (node (ref "C213") (pin "2") (pinfunction "2_2") (pintype "passive"))
      (node (ref "C214") (pin "2") (pinfunction "2_2") (pintype "passive"))
      (node (ref "C215") (pin "2") (pinfunction "2_2") (pintype "passive"))
      (node (ref "C216") (pin "2") (pinfunction "2_2") (pintype "passive"))
      (node (ref "C217") (pin "2") (pinfunction "2_2") (pintype "passive"))
      (node (ref "C218") (pin "2") (pinfunction "2_2") (pintype "passive"))
      (node (ref "C219") (pin "2") (pinfunction "2_2") (pintype "passive"))
      (node (ref "J201") (pin "15") (pinfunction "15_15") (pintype "passive"))
      (node (ref "J201") (pin "18") (pinfunction "18_18") (pintype "passive"))
      (node (ref "J201") (pin "21") (pinfunction "21_21") (pintype "passive"))
      (node (ref "J201") (pin "27") (pinfunction "27_27") (pintype "passive"))
      (node (ref "J201") (pin "29") (pinfunction "29_29") (pintype "passive"))
      (node (ref "J201") (pin "35") (pinfunction "35_35") (pintype "passive"))
      (node (ref "J201") (pin "37") (pinfunction "37_37") (pintype "passive"))
      (node (ref "J201") (pin "4") (pinfunction "4_4") (pintype "passive"))
      (node (ref "J201") (pin "40") (pinfunction "40_40") (pintype "passive"))
      (node (ref "J201") (pin "50") (pinfunction "50_50") (pintype "passive"))
      (node (ref "J201") (pin "53") (pinfunction "53_53") (pintype "passive"))
      (node (ref "J201") (pin "9") (pinfunction "9_9") (pintype "passive"))
      (node (ref "J202") (pin "C5") (pinfunction "GND_C5") (pintype "passive"))
      (node (ref "J202") (pin "S") (pinfunction "SHIELD_S") (pintype "passive"))
      (node (ref "J203") (pin "A1") (pinfunction "GND_A1") (pintype "passive"))
      (node (ref "J203") (pin "A12") (pinfunction "GND_A12") (pintype "passive"))
      (node (ref "J203") (pin "B1") (pinfunction "GND_B1") (pintype "passive"))
      (node (ref "J203") (pin "B12") (pinfunction "GND_B12") (pintype "passive"))
      (node (ref "TP213") (pin "1") (pinfunction "1_1") (pintype "passive"))
      (node (ref "TP214") (pin "1") (pinfunction "1_1") (pintype "passive"))
      (node (ref "U201") (pin "2") (pinfunction "GND_2") (pintype "passive"))
      (node (ref "U201") (pin "26") (pinfunction "GND_26") (pintype "passive"))
      (node (ref "U201") (pin "45") (pinfunction "GND_45") (pintype "passive"))
      (node (ref "U201") (pin "70") (pinfunction "GND_70") (pintype "passive"))
      (node (ref "U201") (pin "95") (pinfunction "GND_95") (pintype "passive"))
      (node (ref "U202") (pin "2") (pinfunction "GND_2") (pintype "passive"))
      (node (ref "U203") (pin "2") (pinfunction "GND_2") (pintype "power_in"))
      (node (ref "U204") (pin "4") (pinfunction "GND_4") (pintype "passive"))
    )
    (net (code "60") (name "Net-(C214-Pad1)") (class "Default")
      (node (ref "C214") (pin "1") (pinfunction "1_1") (pintype "passive"))
      (node (ref "J203") (pin "A4") (pinfunction "VBUS_A4") (pintype "passive"))
      (node (ref "J203") (pin "A9") (pinfunction "VBUS_A9") (pintype "passive"))
      (node (ref "J203") (pin "B4") (pinfunction "VBUS_B4") (pintype "passive"))
      (node (ref "J203") (pin "B9") (pinfunction "VBUS_B9") (pintype "passive"))
    )
    (net (code "61") (name "Net-(D201-Pad2)") (class "Default")
      (node (ref "D201") (pin "2") (pinfunction "2_2") (pintype "passive"))
      (node (ref "R201") (pin "2") (pinfunction "2_2") (pintype "passive"))
    )
    (net (code "62") (name "unconnected-(J201-Pad1)") (class "Default")
      (node (ref "J201") (pin "1") (pinfunction "1_1") (pintype "passive+no_connect"))
    )
    (net (code "63") (name "unconnected-(J201-Pad3)") (class "Default")
      (node (ref "J201") (pin "3") (pinfunction "3_3") (pintype "passive+no_connect"))
    )
    (net (code "64") (name "unconnected-(J201-Pad5)") (class "Default")
      (node (ref "J201") (pin "5") (pinfunction "5_5") (pintype "passive+no_connect"))
    )
    (net (code "65") (name "unconnected-(J201-Pad7)") (class "Default")
      (node (ref "J201") (pin "7") (pinfunction "7_7") (pintype "passive+no_connect"))
    )
    (net (code "66") (name "unconnected-(J201-Pad11)") (class "Default")
      (node (ref "J201") (pin "11") (pinfunction "11_11") (pintype "passive+no_connect"))
    )
    (net (code "67") (name "unconnected-(J201-Pad13)") (class "Default")
      (node (ref "J201") (pin "13") (pinfunction "13_13") (pintype "passive+no_connect"))
    )
    (net (code "68") (name "unconnected-(J201-Pad20)") (class "Default")
      (node (ref "J201") (pin "20") (pinfunction "20_20") (pintype "passive+no_connect"))
    )
    (net (code "69") (name "unconnected-(J201-Pad23)") (class "Default")
      (node (ref "J201") (pin "23") (pinfunction "23_23") (pintype "passive+no_connect"))
    )
    (net (code "70") (name "unconnected-(J201-Pad26)") (class "Default")
      (node (ref "J201") (pin "26") (pinfunction "26_26") (pintype "passive+no_connect"))
    )
    (net (code "71") (name "unconnected-(J201-Pad28)") (class "Default")
      (node (ref "J201") (pin "28") (pinfunction "28_28") (pintype "passive+no_connect"))
    )
    (net (code "72") (name "unconnected-(J201-Pad30)") (class "Default")
      (node (ref "J201") (pin "30") (pinfunction "30_30") (pintype "passive+no_connect"))
    )
    (net (code "73") (name "unconnected-(J201-Pad31)") (class "Default")
      (node (ref "J201") (pin "31") (pinfunction "31_31") (pintype "passive+no_connect"))
    )
    (net (code "74") (name "unconnected-(J201-Pad32)") (class "Default")
      (node (ref "J201") (pin "32") (pinfunction "32_32") (pintype "passive+no_connect"))
    )
    (net (code "75") (name "unconnected-(J201-Pad33)") (class "Default")
      (node (ref "J201") (pin "33") (pinfunction "33_33") (pintype "passive+no_connect"))
    )
    (net (code "76") (name "unconnected-(J201-Pad34)") (class "Default")
      (node (ref "J201") (pin "34") (pinfunction "34_34") (pintype "passive+no_connect"))
    )
    (net (code "77") (name "unconnected-(J201-Pad36)") (class "Default")
      (node (ref "J201") (pin "36") (pinfunction "36_36") (pintype "passive+no_connect"))
    )
    (net (code "78") (name "unconnected-(J201-Pad38)") (class "Default")
      (node (ref "J201") (pin "38") (pinfunction "38_38") (pintype "passive+no_connect"))
    )
    (net (code "79") (name "unconnected-(J201-Pad42)") (class "Default")
      (node (ref "J201") (pin "42") (pinfunction "42_42") (pintype "passive+no_connect"))
    )
    (net (code "80") (name "unconnected-(J201-Pad43)") (class "Default")
      (node (ref "J201") (pin "43") (pinfunction "43_43") (pintype "passive+no_connect"))
    )
    (net (code "81") (name "unconnected-(J201-Pad44)") (class "Default")
      (node (ref "J201") (pin "44") (pinfunction "44_44") (pintype "passive+no_connect"))
    )
    (net (code "82") (name "unconnected-(J201-Pad45)") (class "Default")
      (node (ref "J201") (pin "45") (pinfunction "45_45") (pintype "passive+no_connect"))
    )
    (net (code "83") (name "unconnected-(J201-Pad46)") (class "Default")
      (node (ref "J201") (pin "46") (pinfunction "46_46") (pintype "passive+no_connect"))
    )
    (net (code "84") (name "unconnected-(J201-Pad47)") (class "Default")
      (node (ref "J201") (pin "47") (pinfunction "47_47") (pintype "passive+no_connect"))
    )
    (net (code "85") (name "unconnected-(J201-Pad48)") (class "Default")
      (node (ref "J201") (pin "48") (pinfunction "48_48") (pintype "passive+no_connect"))
    )
    (net (code "86") (name "unconnected-(J201-Pad49)") (class "Default")
      (node (ref "J201") (pin "49") (pinfunction "49_49") (pintype "passive+no_connect"))
    )
    (net (code "87") (name "unconnected-(J201-Pad51)") (class "Default")
      (node (ref "J201") (pin "51") (pinfunction "51_51") (pintype "passive+no_connect"))
    )
    (net (code "88") (name "unconnected-(J202-VPP-PadC6)") (class "Default")
      (node (ref "J202") (pin "C6") (pinfunction "VPP_C6") (pintype "passive+no_connect"))
    )
    (net (code "89") (name "unconnected-(J203-CC1-PadA5)") (class "Default")
      (node (ref "J203") (pin "A5") (pinfunction "CC1_A5") (pintype "passive+no_connect"))
    )
    (net (code "90") (name "unconnected-(J203-CC2-PadB5)") (class "Default")
      (node (ref "J203") (pin "B5") (pinfunction "CC2_B5") (pintype "passive+no_connect"))
    )
    (net (code "91") (name "unconnected-(J203-SBU1-PadA8)") (class "Default")
      (node (ref "J203") (pin "A8") (pinfunction "SBU1_A8") (pintype "passive+no_connect"))
    )
    (net (code "92") (name "unconnected-(J203-SBU2-PadB8)") (class "Default")
      (node (ref "J203") (pin "B8") (pinfunction "SBU2_B8") (pintype "passive+no_connect"))
    )
    (net (code "93") (name "unconnected-(U201A-PA18{slash}RD{slash}PCK2{slash}A14{slash}AD1-Pad14)") (class "Default")
      (node (ref "U201") (pin "14") (pinfunction "PA18/RD/PCK2/A14/AD1_14") (pintype "passive+no_connect"))
    )
    (net (code "94") (name "unconnected-(U201A-PA19{slash}RK{slash}PWML0{slash}A15{slash}AD2{slash}WKUP9-Pad18)") (class "Default")
      (node (ref "U201") (pin "18") (pinfunction "PA19/RK/PWML0/A15/AD2/WKUP9_18") (pintype "passive+no_connect"))
    )
    (net (code "95") (name "unconnected-(U201A-PA20{slash}RF{slash}PWML1{slash}A16{slash}AD3{slash}WKUP10-Pad24)") (class "Default")
      (node (ref "U201") (pin "24") (pinfunction "PA20/RF/PWML1/A16/AD3/WKUP10_24") (pintype "passive+no_connect"))
    )
    (net (code "96") (name "unconnected-(U201A-PA24{slash}RTS1{slash}PWMH1{slash}A20{slash}PIODC0-Pad34)") (class "Default")
      (node (ref "U201") (pin "34") (pinfunction "PA24/RTS1/PWMH1/A20/PIODC0_34") (pintype "passive+no_connect"))
    )
    (net (code "97") (name "unconnected-(U201A-PA25{slash}CTS1{slash}PWMH2{slash}A23{slash}PIODC1-Pad38)") (class "Default")
      (node (ref "U201") (pin "38") (pinfunction "PA25/CTS1/PWMH2/A23/PIODC1_38") (pintype "passive+no_connect"))
    )
    (net (code "98") (name "unconnected-(U201A-PA27{slash}PIODC3{slash}MCDA3{slash}TIOB2{slash}DTR1-Pad57)") (class "Default")
      (node (ref "U201") (pin "57") (pinfunction "PA27/PIODC3/MCDA3/TIOB2/DTR1_57") (pintype "passive+no_connect"))
    )
    (net (code "99") (name "unconnected-(U201A-PA28{slash}PIODC4{slash}MCCDA{slash}TCLK1{slash}DSR1-Pad59)") (class "Default")
      (node (ref "U201") (pin "59") (pinfunction "PA28/PIODC4/MCCDA/TCLK1/DSR1_59") (pintype "passive+no_connect"))
    )
    (net (code "100") (name "unconnected-(U201C-PC0{slash}D0{slash}PWML0-Pad25)") (class "Default")
      (node (ref "U201") (pin "25") (pinfunction "PC0/D0/PWML0_25") (pintype "passive+no_connect"))
    )
    (net (code "101") (name "unconnected-(U201C-PC1{slash}D1{slash}PWML1-Pad47)") (class "Default")
      (node (ref "U201") (pin "47") (pinfunction "PC1/D1/PWML1_47") (pintype "passive+no_connect"))
    )
    (net (code "102") (name "unconnected-(U201C-PC2{slash}D2{slash}PWML2-Pad43)") (class "Default")
      (node (ref "U201") (pin "43") (pinfunction "PC2/D2/PWML2_43") (pintype "passive+no_connect"))
    )
    (net (code "103") (name "unconnected-(U201C-PC3{slash}D3{slash}PWML3-Pad40)") (class "Default")
      (node (ref "U201") (pin "40") (pinfunction "PC3/D3/PWML3_40") (pintype "passive+no_connect"))
    )
    (net (code "104") (name "unconnected-(U201C-PC4{slash}D4{slash}NPCS1-Pad37)") (class "Default")
      (node (ref "U201") (pin "37") (pinfunction "PC4/D4/NPCS1_37") (pintype "passive+no_connect"))
    )
    (net (code "105") (name "unconnected-(U201C-PC5{slash}D5-Pad35)") (class "Default")
      (node (ref "U201") (pin "35") (pinfunction "PC5/D5_35") (pintype "passive+no_connect"))
    )
    (net (code "106") (name "unconnected-(U201C-PC6{slash}D6-Pad32)") (class "Default")
      (node (ref "U201") (pin "32") (pinfunction "PC6/D6_32") (pintype "passive+no_connect"))
    )
    (net (code "107") (name "unconnected-(U201C-PC7{slash}D7-Pad29)") (class "Default")
      (node (ref "U201") (pin "29") (pinfunction "PC7/D7_29") (pintype "passive+no_connect"))
    )
    (net (code "108") (name "unconnected-(U201C-PC8{slash}NWE-Pad58)") (class "Default")
      (node (ref "U201") (pin "58") (pinfunction "PC8/NWE_58") (pintype "passive+no_connect"))
    )
    (net (code "109") (name "unconnected-(U201C-PC9{slash}NANDOE-Pad62)") (class "Default")
      (node (ref "U201") (pin "62") (pinfunction "PC9/NANDOE_62") (pintype "passive+no_connect"))
    )
    (net (code "110") (name "unconnected-(U201C-PC10{slash}PWML0{slash}D0-Pad65)") (class "Default")
      (node (ref "U201") (pin "65") (pinfunction "PC10/PWML0/D0_65") (pintype "passive+no_connect"))
    )
    (net (code "111") (name "unconnected-(U201C-PC11{slash}NRD-Pad68)") (class "Default")
      (node (ref "U201") (pin "68") (pinfunction "PC11/NRD_68") (pintype "passive+no_connect"))
    )
    (net (code "112") (name "unconnected-(U201C-PC12{slash}NCS3{slash}AD12-Pad23)") (class "Default")
      (node (ref "U201") (pin "23") (pinfunction "PC12/NCS3/AD12_23") (pintype "passive+no_connect"))
    )
    (net (code "113") (name "unconnected-(U201C-PC13{slash}NWAIT{slash}PWML0{slash}AD10-Pad21)") (class "Default")
      (node (ref "U201") (pin "21") (pinfunction "PC13/NWAIT/PWML0/AD10_21") (pintype "passive+no_connect"))
    )
    (net (code "114") (name "unconnected-(U201C-PC14{slash}NCS0-Pad71)") (class "Default")
      (node (ref "U201") (pin "71") (pinfunction "PC14/NCS0_71") (pintype "passive+no_connect"))
    )
    (net (code "115") (name "unconnected-(U201C-PC15{slash}NCS1{slash}PWML1{slash}AD11-Pad19)") (class "Default")
      (node (ref "U201") (pin "19") (pinfunction "PC15/NCS1/PWML1/AD11_19") (pintype "passive+no_connect"))
    )
    (net (code "116") (name "unconnected-(U201C-PC16{slash}NANDALE{slash}A21-Pad73)") (class "Default")
      (node (ref "U201") (pin "73") (pinfunction "PC16/NANDALE/A21_73") (pintype "passive+no_connect"))
    )
    (net (code "117") (name "unconnected-(U201C-PC17{slash}NANDCLE{slash}A22{slash}-Pad75)") (class "Default")
      (node (ref "U201") (pin "75") (pinfunction "PC17/NANDCLE/A22/_75") (pintype "passive+no_connect"))
    )
    (net (code "118") (name "unconnected-(U201C-PC18{slash}PWMH0{slash}A0-Pad78)") (class "Default")
      (node (ref "U201") (pin "78") (pinfunction "PC18/PWMH0/A0_78") (pintype "passive+no_connect"))
    )
    (net (code "119") (name "unconnected-(U201C-PC19{slash}PWMH1{slash}A1-Pad80)") (class "Default")
      (node (ref "U201") (pin "80") (pinfunction "PC19/PWMH1/A1_80") (pintype "passive+no_connect"))
    )
    (net (code "120") (name "unconnected-(U201C-PC20{slash}PWMH2{slash}A2-Pad82)") (class "Default")
      (node (ref "U201") (pin "82") (pinfunction "PC20/PWMH2/A2_82") (pintype "passive+no_connect"))
    )
    (net (code "121") (name "unconnected-(U201C-PC21{slash}PWMH3{slash}A3-Pad84)") (class "Default")
      (node (ref "U201") (pin "84") (pinfunction "PC21/PWMH3/A3_84") (pintype "passive+no_connect"))
    )
    (net (code "122") (name "unconnected-(U201C-PC22{slash}PWML3{slash}A4-Pad86)") (class "Default")
      (node (ref "U201") (pin "86") (pinfunction "PC22/PWML3/A4_86") (pintype "passive+no_connect"))
    )
    (net (code "123") (name "unconnected-(U201C-PC23{slash}TIOA3{slash}A5-Pad90)") (class "Default")
      (node (ref "U201") (pin "90") (pinfunction "PC23/TIOA3/A5_90") (pintype "passive+no_connect"))
    )
    (net (code "124") (name "unconnected-(U201C-PC27{slash}A9{slash}TIOB4-Pad17)") (class "Default")
      (node (ref "U201") (pin "17") (pinfunction "PC27/A9/TIOB4_17") (pintype "passive+no_connect"))
    )
    (net (code "125") (name "unconnected-(U201C-PC28{slash}TCLK4{slash}A10-Pad54)") (class "Default")
      (node (ref "U201") (pin "54") (pinfunction "PC28/TCLK4/A10_54") (pintype "passive+no_connect"))
    )
    (net (code "126") (name "unconnected-(U201D-JTAGSEL-Pad77)") (class "Default")
      (node (ref "U201") (pin "77") (pinfunction "JTAGSEL_77") (pintype "passive+no_connect"))
    )
  )
)
